# Hoja_Control.net
KiCad netlist of a schematic drawn in Altium Designer
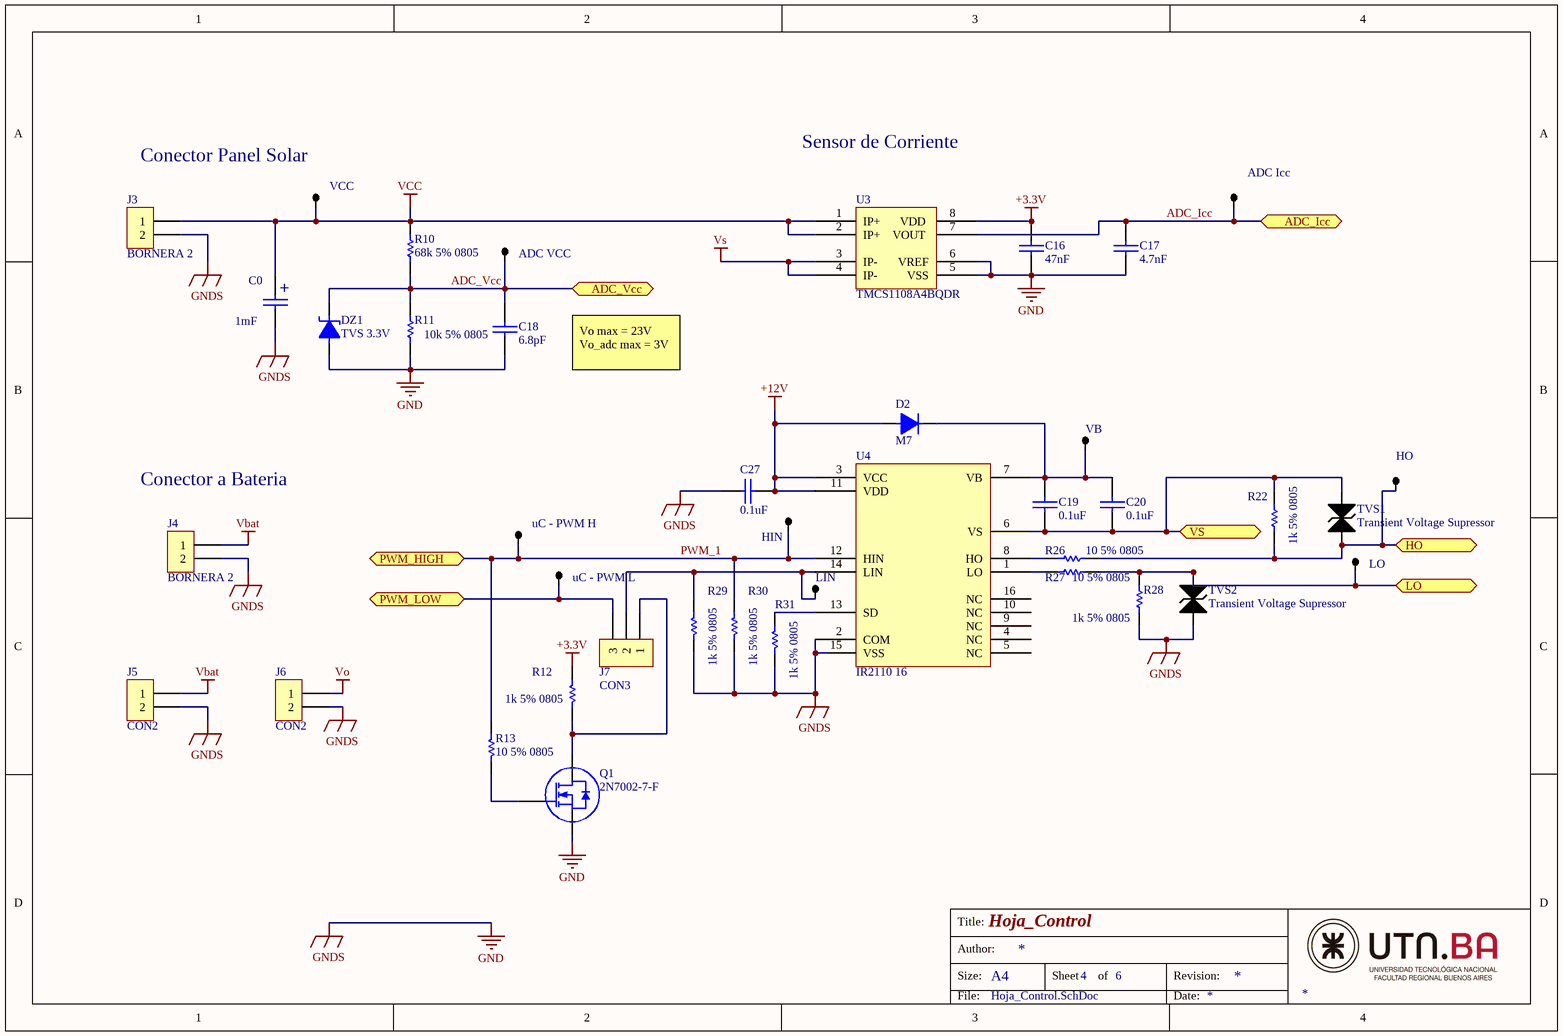
[diagram p0: Hoja_Control.SchDoc]

(export (version "E")
  (design (tool "Eeschema 10.0.6"))
  (components
    (comp (ref "ADC Icc")
      (value "ADC Icc")
      (footprint "TPTH")
      (libsource (lib "Libreria_Casera") (part "TP"))
    )
    (comp (ref "ADC VCC")
      (value "ADC VCC")
      (footprint "TPTH")
      (libsource (lib "Libreria_Casera") (part "TP"))
    )
    (comp (ref "C0") (value "1mF") (footprint "CAPSMD8x8.3") (libsource (lib "LIBEBAL") (part "CAPPOL")))
    (comp (ref "C16") (value "47nF") (footprint "0805") (libsource (lib "Libreria_Casera") (part "CAP")))
    (comp (ref "C17") (value "4.7nF") (footprint "0805") (libsource (lib "Libreria_Casera") (part "CAP")))
    (comp (ref "C18") (value "6.8pF") (footprint "0805") (libsource (lib "Libreria_Casera") (part "CAP")))
    (comp (ref "C19")
      (value "0.1uF")
      (footprint "0805")
      (description "CAP CER 0.1UF X7R 0805")
      (libsource (lib "Libreria_Casera") (part "CAP"))
    )
    (comp (ref "C20")
      (value "0.1uF")
      (footprint "0805")
      (description "CAP CER 0.1UF X7R 0805")
      (libsource (lib "Libreria_Casera") (part "CAP"))
    )
    (comp (ref "C27")
      (value "0.1uF")
      (footprint "0805")
      (description "CAP CER 0.1UF X7R 0805")
      (libsource (lib "Libreria_Casera") (part "CAP"))
    )
    (comp (ref "D2")
      (value "M7")
      (footprint "DO-214AC")
      (description "Diodos Estándar 1000 V 1A Montaje en superficie SMA")
      (libsource (lib "Libreria_Casera") (part "DIODO"))
    )
    (comp (ref "DZ1")
      (value "TVS 3.3V")
      (footprint "sod123")
      (libsource (lib "Libreria_Casera") (part "DIODO ZENER"))
    )
    (comp (ref "HIN") (value "HIN") (footprint "TPTH") (libsource (lib "Libreria_Casera") (part "TP")))
    (comp (ref "HO") (value "HO") (footprint "TPTH") (libsource (lib "Libreria_Casera") (part "TP")))
    (comp (ref "J3")
      (value "BORNERA 2")
      (footprint "Bornera2_DegsonH")
      (libsource (lib "Libreria_Casera") (part "BORNERA 2"))
    )
    (comp (ref "J4")
      (value "BORNERA 2")
      (footprint "Bornera2_DegsonH")
      (libsource (lib "Libreria_Casera") (part "BORNERA 2"))
    )
    (comp (ref "J5") (value "CON2") (footprint "SIP2") (libsource (lib "Libreria_Casera") (part "CON2")))
    (comp (ref "J6") (value "CON2") (footprint "SIP2") (libsource (lib "Libreria_Casera") (part "CON2")))
    (comp (ref "J7") (value "CON3") (footprint "SIP3") (libsource (lib "Libreria_Casera") (part "CON3")))
    (comp (ref "LIN") (value "LIN") (footprint "TPTH") (libsource (lib "Libreria_Casera") (part "TP")))
    (comp (ref "LO") (value "LO") (footprint "TPTH") (libsource (lib "Libreria_Casera") (part "TP")))
    (comp (ref "Q1")
      (value "2N7002-7-F")
      (footprint "SOT23")
      (description "Canal N Montaje en superficie 60 V 115mA (Ta) 370mW (Ta) SOT-23-3")
      (libsource (lib "Libreria_Casera") (part "MOSFET N"))
    )
    (comp (ref "R10")
      (value "68k 5% 0805")
      (footprint "0805")
      (libsource (lib "Libreria_Casera") (part "RES"))
    )
    (comp (ref "R11")
      (value "10k 5% 0805")
      (footprint "0805")
      (libsource (lib "Libreria_Casera") (part "RES"))
    )
    (comp (ref "R12")
      (value "1k 5% 0805")
      (footprint "0805")
      (libsource (lib "Libreria_Casera") (part "RES"))
    )
    (comp (ref "R13")
      (value "10 5% 0805")
      (footprint "0805")
      (libsource (lib "Libreria_Casera") (part "RES"))
    )
    (comp (ref "R22")
      (value "1k 5% 0805")
      (footprint "0805")
      (libsource (lib "Libreria_Casera") (part "RES"))
    )
    (comp (ref "R26")
      (value "10 5% 0805")
      (footprint "0805")
      (libsource (lib "Libreria_Casera") (part "RES"))
    )
    (comp (ref "R27")
      (value "10 5% 0805")
      (footprint "0805")
      (libsource (lib "Libreria_Casera") (part "RES"))
    )
    (comp (ref "R28")
      (value "1k 5% 0805")
      (footprint "0805")
      (libsource (lib "Libreria_Casera") (part "RES"))
    )
    (comp (ref "R29")
      (value "1k 5% 0805")
      (footprint "0805")
      (libsource (lib "Libreria_Casera") (part "RES"))
    )
    (comp (ref "R30")
      (value "1k 5% 0805")
      (footprint "0805")
      (libsource (lib "Libreria_Casera") (part "RES"))
    )
    (comp (ref "R31")
      (value "1k 5% 0805")
      (footprint "0805")
      (libsource (lib "Libreria_Casera") (part "RES"))
    )
    (comp (ref "TVS1")
      (value "Transient Voltage Supressor")
      (footprint "SOD323")
      (libsource (lib "Libreria_Casera") (part "TVS"))
    )
    (comp (ref "TVS2")
      (value "Transient Voltage Supressor")
      (footprint "SOD323")
      (libsource (lib "Libreria_Casera") (part "TVS"))
    )
    (comp (ref "U3")
      (value "TMCS1108A4BQDR")
      (footprint "SOIC8")
      (description "Sensores de corriente 1 canal Efecto Hall Bidireccional 8-SOIC (ancho 0.154\", 3.90mm)")
      (libsource (lib "Libreria_Casera") (part "MLX91221KDC"))
    )
    (comp (ref "U4")
      (value "IR2110 16")
      (footprint "SOIC16W")
      (description "Medio puente controladores de compuerta IC No inversor 14-DIP")
      (libsource (lib "Libreria_Casera") (part "IR2110 16"))
    )
    (comp (ref "uC - PWM H")
      (value "PWM L")
      (footprint "TPTH")
      (libsource (lib "Libreria_Casera") (part "TP"))
    )
    (comp (ref "uC - PWM L")
      (value "PWM H")
      (footprint "TPTH")
      (libsource (lib "Libreria_Casera") (part "TP"))
    )
    (comp (ref "VB") (value "VB") (footprint "TPTH") (libsource (lib "Libreria_Casera") (part "TP")))
    (comp (ref "VCC") (value "VCC") (footprint "TPTH") (libsource (lib "Libreria_Casera") (part "TP")))
  )
  (nets
    (net (code "1") (name "+3.3V") (class "Default")
      (node (ref "C16") (pin "1") (pinfunction "1_1") (pintype "passive"))
      (node (ref "R12") (pin "2") (pinfunction "2_2") (pintype "passive"))
      (node (ref "U3") (pin "8") (pinfunction "VDD_8") (pintype "passive"))
    )
    (net (code "2") (name "+12V") (class "Default")
      (node (ref "C27") (pin "1") (pinfunction "1_1") (pintype "passive"))
      (node (ref "D2") (pin "1") (pinfunction "1_1") (pintype "passive"))
      (node (ref "U4") (pin "11") (pinfunction "VDD_11") (pintype "passive"))
      (node (ref "U4") (pin "3") (pinfunction "VCC_3") (pintype "passive"))
    )
    (net (code "3") (name "/ADC_Icc") (class "Default")
      (node (ref "ADC Icc") (pin "1") (pinfunction "1_1") (pintype "passive"))
      (node (ref "C17") (pin "1") (pinfunction "1_1") (pintype "passive"))
      (node (ref "U3") (pin "7") (pinfunction "VOUT_7") (pintype "passive"))
    )
    (net (code "4") (name "/ADC_Vcc") (class "Default")
      (node (ref "ADC VCC") (pin "1") (pinfunction "1_1") (pintype "passive"))
      (node (ref "C18") (pin "1") (pinfunction "1_1") (pintype "passive"))
      (node (ref "DZ1") (pin "2") (pinfunction "2_2") (pintype "passive"))
      (node (ref "R10") (pin "1") (pinfunction "1_1") (pintype "passive"))
      (node (ref "R11") (pin "2") (pinfunction "2_2") (pintype "passive"))
    )
    (net (code "5") (name "/HO") (class "Default")
      (node (ref "HO") (pin "1") (pinfunction "1_1") (pintype "passive"))
      (node (ref "R22") (pin "1") (pinfunction "1_1") (pintype "passive"))
      (node (ref "R26") (pin "2") (pinfunction "2_2") (pintype "passive"))
      (node (ref "TVS1") (pin "2") (pinfunction "2_2") (pintype "passive"))
    )
    (net (code "6") (name "/LO") (class "Default")
      (node (ref "LO") (pin "1") (pinfunction "1_1") (pintype "passive"))
      (node (ref "R27") (pin "2") (pinfunction "2_2") (pintype "passive"))
      (node (ref "R28") (pin "2") (pinfunction "2_2") (pintype "passive"))
      (node (ref "TVS2") (pin "1") (pinfunction "1_1") (pintype "passive"))
    )
    (net (code "7") (name "/PWM_1") (class "Default")
      (node (ref "HIN") (pin "1") (pinfunction "1_1") (pintype "passive"))
      (node (ref "R13") (pin "2") (pinfunction "2_2") (pintype "passive"))
      (node (ref "R30") (pin "2") (pinfunction "2_2") (pintype "passive"))
      (node (ref "U4") (pin "12") (pinfunction "HIN_12") (pintype "passive"))
      (node (ref "uC - PWM L") (pin "1") (pinfunction "1_1") (pintype "passive"))
    )
    (net (code "8") (name "/PWM_LOW") (class "Default")
      (node (ref "J7") (pin "3") (pinfunction "3_3") (pintype "passive"))
      (node (ref "uC - PWM H") (pin "1") (pinfunction "1_1") (pintype "passive"))
    )
    (net (code "9") (name "/VS") (class "Default")
      (node (ref "C19") (pin "1") (pinfunction "1_1") (pintype "passive"))
      (node (ref "C20") (pin "1") (pinfunction "1_1") (pintype "passive"))
      (node (ref "R22") (pin "2") (pinfunction "2_2") (pintype "passive"))
      (node (ref "TVS1") (pin "1") (pinfunction "1_1") (pintype "passive"))
      (node (ref "U4") (pin "6") (pinfunction "VS_6") (pintype "passive"))
    )
    (net (code "10") (name "GND") (class "Default")
      (node (ref "C0") (pin "2") (pinfunction "2_2") (pintype "passive"))
      (node (ref "C16") (pin "2") (pinfunction "2_2") (pintype "passive"))
      (node (ref "C17") (pin "2") (pinfunction "2_2") (pintype "passive"))
      (node (ref "C18") (pin "2") (pinfunction "2_2") (pintype "passive"))
      (node (ref "C27") (pin "2") (pinfunction "2_2") (pintype "passive"))
      (node (ref "DZ1") (pin "1") (pinfunction "1_1") (pintype "passive"))
      (node (ref "J3") (pin "2") (pinfunction "2_2") (pintype "passive"))
      (node (ref "J4") (pin "2") (pinfunction "2_2") (pintype "passive"))
      (node (ref "J5") (pin "2") (pinfunction "2_2") (pintype "passive"))
      (node (ref "J6") (pin "2") (pinfunction "2_2") (pintype "passive"))
      (node (ref "Q1") (pin "3") (pinfunction "S_3") (pintype "passive"))
      (node (ref "R11") (pin "1") (pinfunction "1_1") (pintype "passive"))
      (node (ref "R28") (pin "1") (pinfunction "1_1") (pintype "passive"))
      (node (ref "R29") (pin "1") (pinfunction "1_1") (pintype "passive"))
      (node (ref "R30") (pin "1") (pinfunction "1_1") (pintype "passive"))
      (node (ref "R31") (pin "1") (pinfunction "1_1") (pintype "passive"))
      (node (ref "TVS2") (pin "2") (pinfunction "2_2") (pintype "passive"))
      (node (ref "U3") (pin "5") (pinfunction "VSS_5") (pintype "passive"))
      (node (ref "U3") (pin "6") (pinfunction "VREF_6") (pintype "passive"))
      (node (ref "U4") (pin "15") (pinfunction "VSS_15") (pintype "passive"))
      (node (ref "U4") (pin "2") (pinfunction "COM_2") (pintype "passive"))
    )
    (net (code "11") (name "Net-(Q1-D)") (class "Default")
      (node (ref "J7") (pin "1") (pinfunction "1_1") (pintype "passive"))
      (node (ref "Q1") (pin "2") (pinfunction "D_2") (pintype "passive"))
      (node (ref "R12") (pin "1") (pinfunction "1_1") (pintype "passive"))
    )
    (net (code "12") (name "Net-(Q1-G)") (class "Default")
      (node (ref "Q1") (pin "1") (pinfunction "G_1") (pintype "passive"))
      (node (ref "R13") (pin "1") (pinfunction "1_1") (pintype "passive"))
    )
    (net (code "13") (name "Net-(U4-HO)") (class "Default")
      (node (ref "R26") (pin "1") (pinfunction "1_1") (pintype "passive"))
      (node (ref "U4") (pin "8") (pinfunction "HO_8") (pintype "passive"))
    )
    (net (code "14") (name "Net-(U4-LIN)") (class "Default")
      (node (ref "J7") (pin "2") (pinfunction "2_2") (pintype "passive"))
      (node (ref "LIN") (pin "1") (pinfunction "1_1") (pintype "passive"))
      (node (ref "R29") (pin "2") (pinfunction "2_2") (pintype "passive"))
      (node (ref "U4") (pin "14") (pinfunction "LIN_14") (pintype "passive"))
    )
    (net (code "15") (name "Net-(U4-LO)") (class "Default")
      (node (ref "R27") (pin "1") (pinfunction "1_1") (pintype "passive"))
      (node (ref "U4") (pin "1") (pinfunction "LO_1") (pintype "passive"))
    )
    (net (code "16") (name "Net-(U4-SD)") (class "Default")
      (node (ref "R31") (pin "2") (pinfunction "2_2") (pintype "passive"))
      (node (ref "U4") (pin "13") (pinfunction "SD_13") (pintype "passive"))
    )
    (net (code "17") (name "Net-(U4-VB)") (class "Default")
      (node (ref "C19") (pin "2") (pinfunction "2_2") (pintype "passive"))
      (node (ref "C20") (pin "2") (pinfunction "2_2") (pintype "passive"))
      (node (ref "D2") (pin "2") (pinfunction "2_2") (pintype "passive"))
      (node (ref "U4") (pin "7") (pinfunction "VB_7") (pintype "passive"))
      (node (ref "VB") (pin "1") (pinfunction "1_1") (pintype "passive"))
    )
    (net (code "18") (name "VCC") (class "Default")
      (node (ref "C0") (pin "1") (pinfunction "1_1") (pintype "passive"))
      (node (ref "J3") (pin "1") (pinfunction "1_1") (pintype "passive"))
      (node (ref "R10") (pin "2") (pinfunction "2_2") (pintype "passive"))
      (node (ref "U3") (pin "1") (pinfunction "IP+_1") (pintype "passive"))
      (node (ref "U3") (pin "2") (pinfunction "IP+_2") (pintype "passive"))
      (node (ref "VCC") (pin "1") (pinfunction "1_1") (pintype "passive"))
    )
    (net (code "19") (name "Vbat") (class "Default")
      (node (ref "J4") (pin "1") (pinfunction "1_1") (pintype "passive"))
      (node (ref "J5") (pin "1") (pinfunction "1_1") (pintype "passive"))
    )
    (net (code "20") (name "Vo") (class "Default")
      (node (ref "J6") (pin "1") (pinfunction "1_1") (pintype "passive"))
    )
    (net (code "21") (name "Vs") (class "Default")
      (node (ref "U3") (pin "3") (pinfunction "IP-_3") (pintype "passive"))
      (node (ref "U3") (pin "4") (pinfunction "IP-_4") (pintype "passive"))
    )
    (net (code "22") (name "unconnected-(U4-NC-Pad4)") (class "Default")
      (node (ref "U4") (pin "4") (pinfunction "NC_4") (pintype "passive"))
    )
    (net (code "23") (name "unconnected-(U4-NC-Pad5)") (class "Default")
      (node (ref "U4") (pin "5") (pinfunction "NC_5") (pintype "passive"))
    )
    (net (code "24") (name "unconnected-(U4-NC-Pad9)") (class "Default")
      (node (ref "U4") (pin "9") (pinfunction "NC_9") (pintype "passive"))
    )
    (net (code "25") (name "unconnected-(U4-NC-Pad10)") (class "Default")
      (node (ref "U4") (pin "10") (pinfunction "NC_10") (pintype "passive"))
    )
    (net (code "26") (name "unconnected-(U4-NC-Pad16)") (class "Default")
      (node (ref "U4") (pin "16") (pinfunction "NC_16") (pintype "passive"))
    )
  )
)
